# LVDS_IFCA.net
KiCad netlist of a schematic drawn in Altium Designer
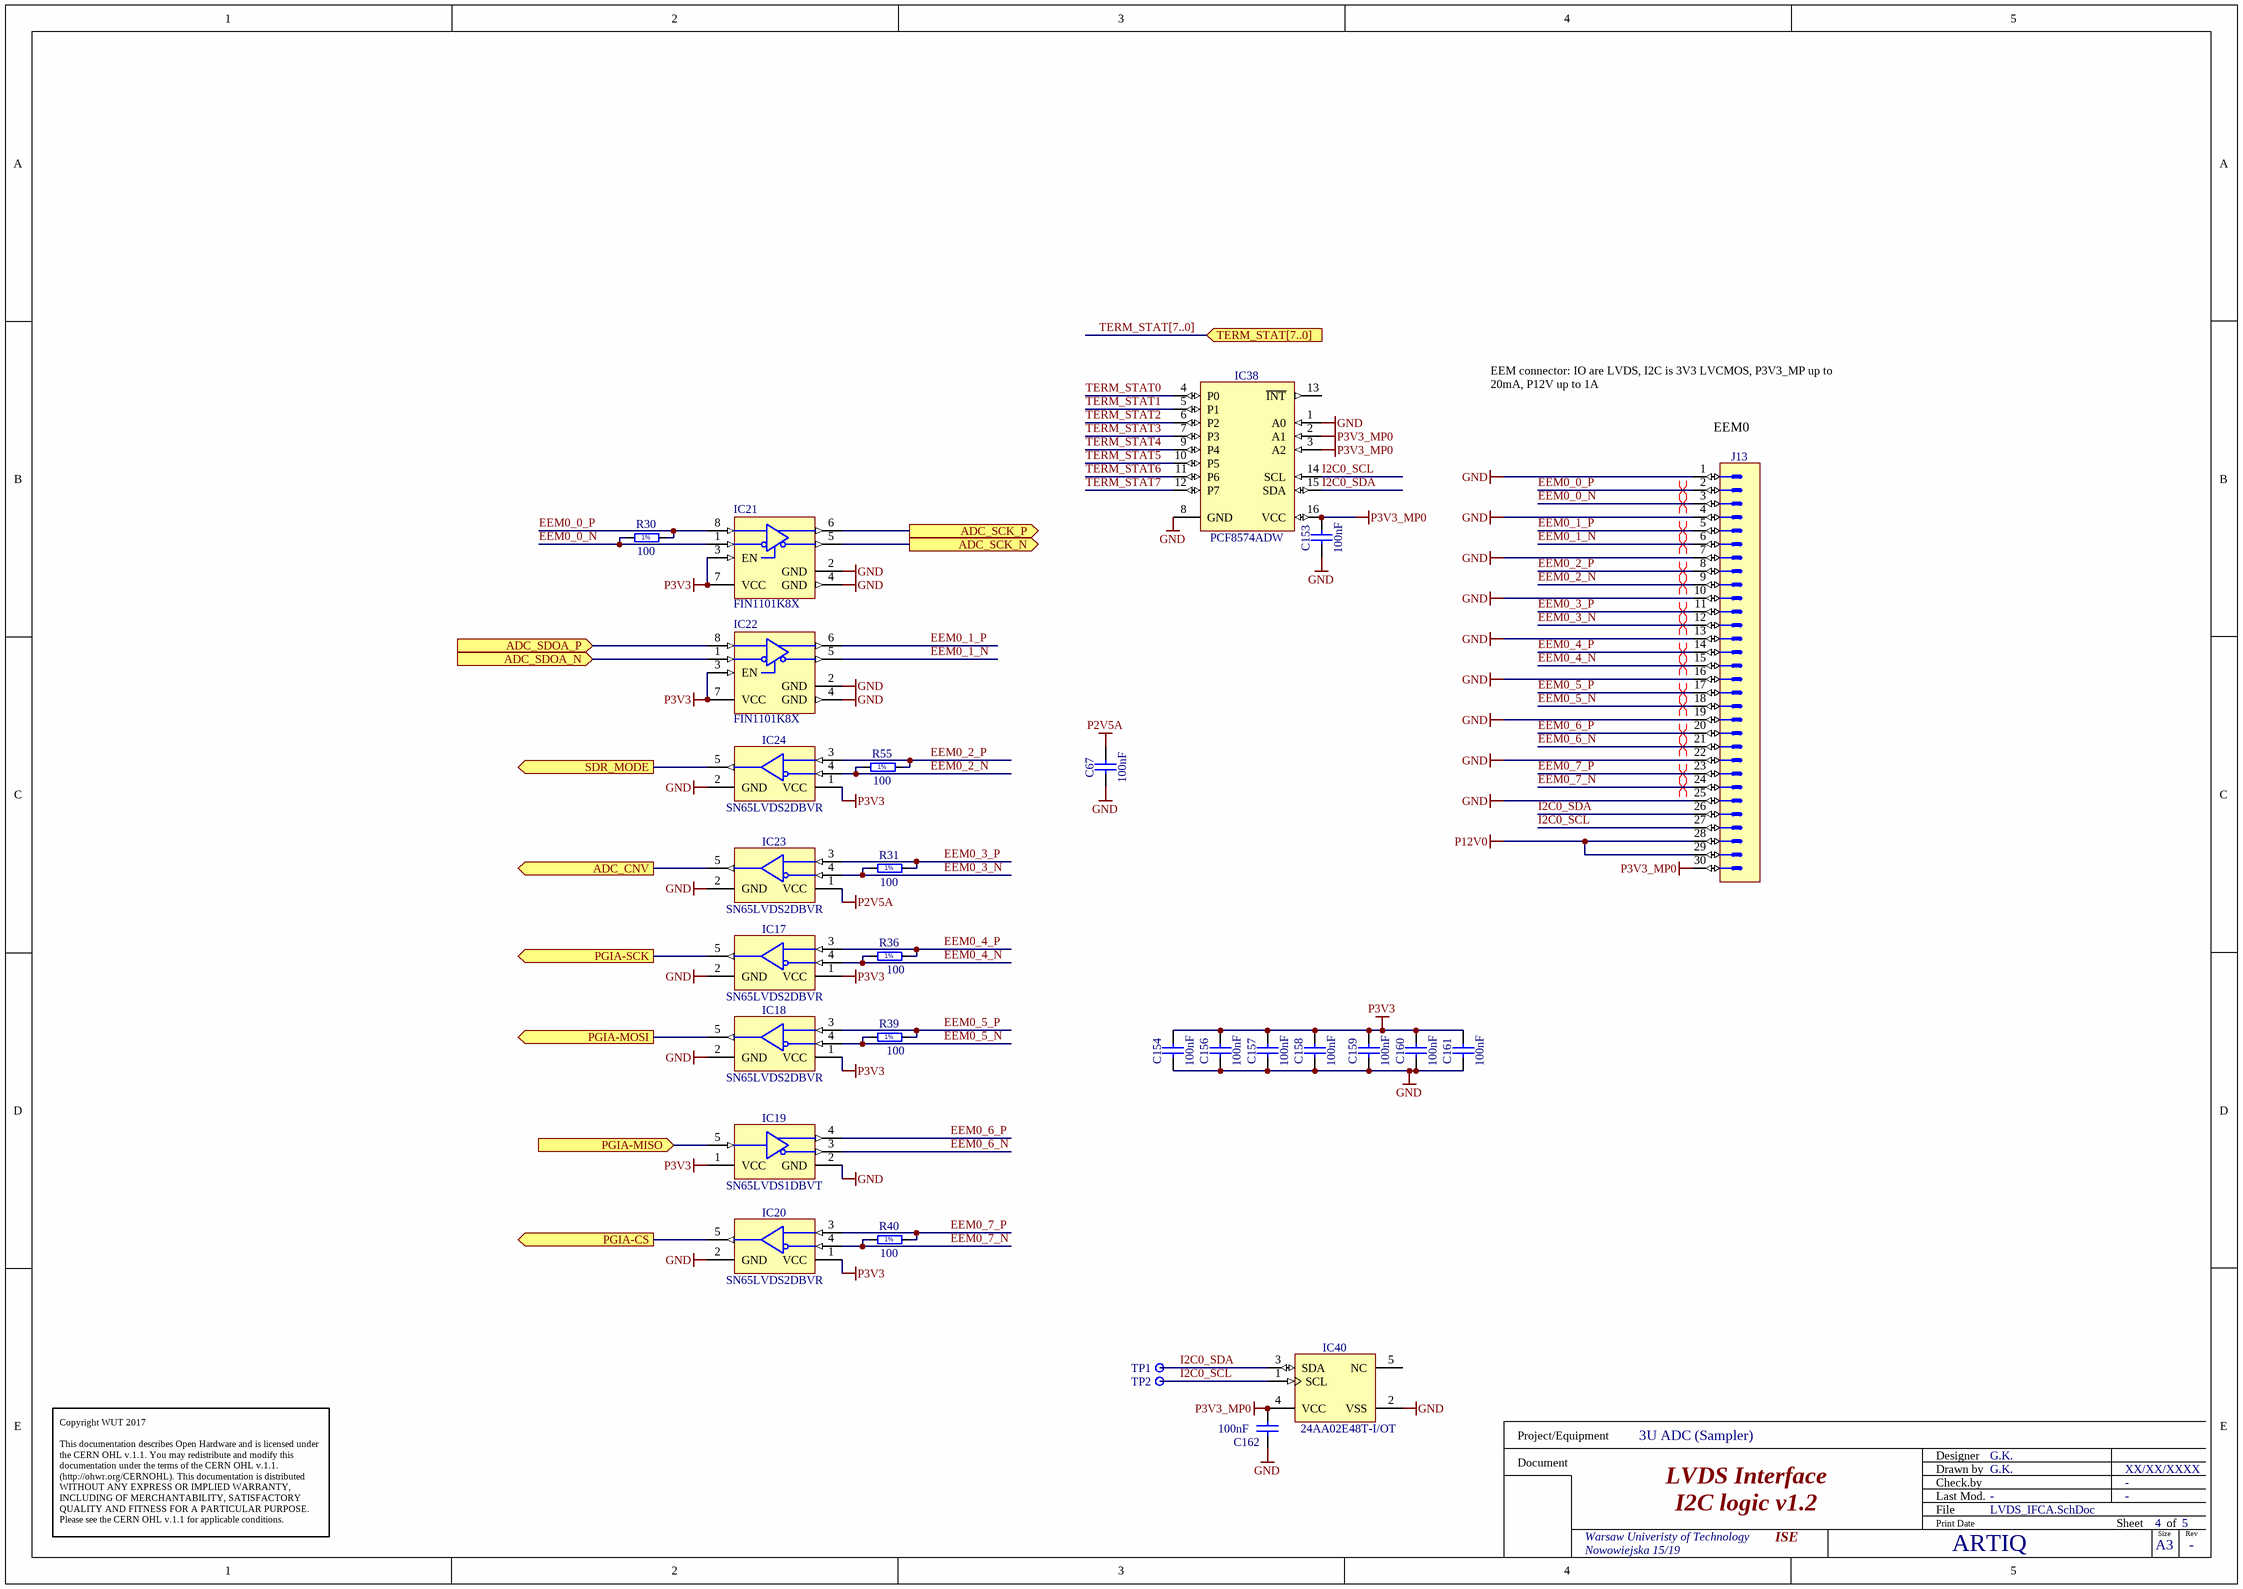
[diagram p0: LVDS_IFCA.SchDoc]

(export (version "E")
  (design (tool "Eeschema 10.0.6"))
  (components
    (comp (ref "C67")
      (value "100nF")
      (footprint "CAPC1005X55N")
      (description "Non-polarised capacitor")
      (fields
        (field (name "PART NUMBER") "CC0402_100NF_16V_10%_X5R")
        (field (name "VOLTAGE") "16V")
        (field (name "AUTHOR") "CERN DEM JLC")
      )
      (libsource (lib "Capacitors") (part "Capacitor - non polarized"))
    )
    (comp (ref "C153")
      (value "100nF")
      (footprint "CAPC1005X55N")
      (description "Non-polarised capacitor")
      (fields
        (field (name "PART NUMBER") "CC0402_100NF_16V_10%_X5R")
        (field (name "VOLTAGE") "16V")
        (field (name "AUTHOR") "CERN DEM JLC")
      )
      (libsource (lib "Capacitors") (part "Capacitor - non polarized"))
    )
    (comp (ref "C154")
      (value "100nF")
      (footprint "CAPC1005X55N")
      (description "Non-polarised capacitor")
      (fields
        (field (name "PART NUMBER") "CC0402_100NF_16V_10%_X5R")
        (field (name "VOLTAGE") "16V")
        (field (name "AUTHOR") "CERN DEM JLC")
      )
      (libsource (lib "Capacitors") (part "Capacitor - non polarized"))
    )
    (comp (ref "C156")
      (value "100nF")
      (footprint "CAPC1005X55N")
      (description "Non-polarised capacitor")
      (fields
        (field (name "PART NUMBER") "CC0402_100NF_16V_10%_X5R")
        (field (name "VOLTAGE") "16V")
        (field (name "AUTHOR") "CERN DEM JLC")
      )
      (libsource (lib "Capacitors") (part "Capacitor - non polarized"))
    )
    (comp (ref "C157")
      (value "100nF")
      (footprint "CAPC1005X55N")
      (description "Non-polarised capacitor")
      (fields
        (field (name "PART NUMBER") "CC0402_100NF_16V_10%_X5R")
        (field (name "VOLTAGE") "16V")
        (field (name "AUTHOR") "CERN DEM JLC")
      )
      (libsource (lib "Capacitors") (part "Capacitor - non polarized"))
    )
    (comp (ref "C158")
      (value "100nF")
      (footprint "CAPC1005X55N")
      (description "Non-polarised capacitor")
      (fields
        (field (name "PART NUMBER") "CC0402_100NF_16V_10%_X5R")
        (field (name "VOLTAGE") "16V")
        (field (name "AUTHOR") "CERN DEM JLC")
      )
      (libsource (lib "Capacitors") (part "Capacitor - non polarized"))
    )
    (comp (ref "C159")
      (value "100nF")
      (footprint "CAPC1005X55N")
      (description "Non-polarised capacitor")
      (fields
        (field (name "PART NUMBER") "CC0402_100NF_16V_10%_X5R")
        (field (name "VOLTAGE") "16V")
        (field (name "AUTHOR") "CERN DEM JLC")
      )
      (libsource (lib "Capacitors") (part "Capacitor - non polarized"))
    )
    (comp (ref "C160")
      (value "100nF")
      (footprint "CAPC1005X55N")
      (description "Non-polarised capacitor")
      (fields
        (field (name "PART NUMBER") "CC0402_100NF_16V_10%_X5R")
        (field (name "VOLTAGE") "16V")
        (field (name "AUTHOR") "CERN DEM JLC")
      )
      (libsource (lib "Capacitors") (part "Capacitor - non polarized"))
    )
    (comp (ref "C161")
      (value "100nF")
      (footprint "CAPC1005X55N")
      (description "Non-polarised capacitor")
      (fields
        (field (name "PART NUMBER") "CC0402_100NF_16V_10%_X5R")
        (field (name "VOLTAGE") "16V")
        (field (name "AUTHOR") "CERN DEM JLC")
      )
      (libsource (lib "Capacitors") (part "Capacitor - non polarized"))
    )
    (comp (ref "C162")
      (value "100nF")
      (footprint "CAPC1005X55N")
      (description "Non-polarised capacitor")
      (fields
        (field (name "PART NUMBER") "CC0402_100NF_16V_10%_X5R")
        (field (name "VOLTAGE") "16V")
        (field (name "AUTHOR") "CERN DEM JLC")
      )
      (libsource (lib "Capacitors") (part "Capacitor - non polarized"))
    )
    (comp (ref "IC17")
      (value "SN65LVDS2DBVR")
      (footprint "SOT95P280X145-5N")
      (description "High-Speed Differential Line Receiver")
      (fields (field (name "MANUFACTURER") "TEXAS INSTRUMENTS") (field (name "AUTHOR") "CERN DEM JLC"))
      (libsource (lib "ICs And Semiconductors") (part "SN65LVDS2DBV"))
    )
    (comp (ref "IC18")
      (value "SN65LVDS2DBVR")
      (footprint "SOT95P280X145-5N")
      (description "High-Speed Differential Line Receiver")
      (fields (field (name "MANUFACTURER") "TEXAS INSTRUMENTS") (field (name "AUTHOR") "CERN DEM JLC"))
      (libsource (lib "ICs And Semiconductors") (part "SN65LVDS2DBV"))
    )
    (comp (ref "IC19")
      (value "SN65LVDS1DBVT")
      (footprint "SOT95P280X145-5N")
      (description "High-Speed Differential Line Driver")
      (fields (field (name "MANUFACTURER") "TEXAS INSTRUMENTS") (field (name "AUTHOR") "CERN DEM JLC"))
      (libsource (lib "ICs And Semiconductors") (part "SN65LVDS1DBV"))
    )
    (comp (ref "IC20")
      (value "SN65LVDS2DBVR")
      (footprint "SOT95P280X145-5N")
      (description "High-Speed Differential Line Receiver")
      (fields (field (name "MANUFACTURER") "TEXAS INSTRUMENTS") (field (name "AUTHOR") "CERN DEM JLC"))
      (libsource (lib "ICs And Semiconductors") (part "SN65LVDS2DBV"))
    )
    (comp (ref "IC21")
      (value "FIN1101K8X")
      (footprint "SOP50P310X90-8N")
      (description "LVDS Single Port High Speed Repeater")
      (fields (field (name "MANUFACTURER") "FAIRCHILD SEMICONDUCTOR") (field (name "AUTHOR") "CERN DEM JLC"))
      (libsource (lib "ICs And Semiconductors") (part "FIN1101K8X"))
    )
    (comp (ref "IC22")
      (value "FIN1101K8X")
      (footprint "SOP50P310X90-8N")
      (description "LVDS Single Port High Speed Repeater")
      (fields (field (name "MANUFACTURER") "FAIRCHILD SEMICONDUCTOR") (field (name "AUTHOR") "CERN DEM JLC"))
      (libsource (lib "ICs And Semiconductors") (part "FIN1101K8X"))
    )
    (comp (ref "IC23")
      (value "SN65LVDS2DBVR")
      (footprint "SOT95P280X145-5N")
      (description "High-Speed Differential Line Receiver")
      (fields (field (name "MANUFACTURER") "TEXAS INSTRUMENTS") (field (name "AUTHOR") "CERN DEM JLC"))
      (libsource (lib "ICs And Semiconductors") (part "SN65LVDS2DBV"))
    )
    (comp (ref "IC24")
      (value "SN65LVDS2DBVR")
      (footprint "SOT95P280X145-5N")
      (description "High-Speed Differential Line Receiver")
      (fields (field (name "MANUFACTURER") "TEXAS INSTRUMENTS") (field (name "AUTHOR") "CERN DEM JLC"))
      (libsource (lib "ICs And Semiconductors") (part "SN65LVDS2DBV"))
    )
    (comp (ref "IC38")
      (value "PCF8574ADW")
      (footprint "SOIC127P1030X265-16N")
      (description "Remote 8-bit I/O Expander For I2C Bus")
      (fields (field (name "MANUFACTURER") "TEXAS INSTRUMENTS") (field (name "AUTHOR") "CERN DEM JLC"))
      (libsource (lib "ICs And Semiconductors") (part "PCF8574ADW"))
    )
    (comp (ref "IC40")
      (value "24AA02E48T-I/OT")
      (footprint "SOT95P280X145-5N")
      (description "1.7V-5.5V, 2K I2C Serial EEPROM With EUI-48 Node Identity")
      (fields (field (name "MANUFACTURER") "MICROCHIP TECHNOLOGY") (field (name "AUTHOR") "CERN DEM MR"))
      (libsource (lib "ICs And Semiconductors") (part "24AA02E48T-I/OT"))
    )
    (comp (ref "J13")
      (value "~")
      (footprint "3M_N2530-6002RB")
      (description "Connector 30 Male")
      (fields
        (field (name "PART NUMBER") "3M_N2530-6002RB")
        (field (name "MANUFACTURER") "3M")
        (field (name "AUTHOR") "CERN DEM JLC")
      )
      (libsource (lib "Connectors") (part "Connector 30 Male"))
    )
    (comp (ref "R30")
      (value "100")
      (footprint "RESC1005X40N")
      (description "Resistor - 1%")
      (fields
        (field (name "PART NUMBER") "R0402_100R_1%_0.1W_100PPM")
        (field (name "POWER") "0.1W")
        (field (name "AUTHOR") "CERN DEM JLC")
      )
      (libsource (lib "Resistors") (part "Resistor - 1%"))
    )
    (comp (ref "R31")
      (value "100")
      (footprint "RESC1005X40N")
      (description "Resistor - 1%")
      (fields
        (field (name "PART NUMBER") "R0402_100R_1%_0.1W_100PPM")
        (field (name "POWER") "0.1W")
        (field (name "AUTHOR") "CERN DEM JLC")
      )
      (libsource (lib "Resistors") (part "Resistor - 1%"))
    )
    (comp (ref "R36")
      (value "100")
      (footprint "RESC1005X40N")
      (description "Resistor - 1%")
      (fields
        (field (name "PART NUMBER") "R0402_100R_1%_0.1W_100PPM")
        (field (name "POWER") "0.1W")
        (field (name "AUTHOR") "CERN DEM JLC")
      )
      (libsource (lib "Resistors") (part "Resistor - 1%"))
    )
    (comp (ref "R39")
      (value "100")
      (footprint "RESC1005X40N")
      (description "Resistor - 1%")
      (fields
        (field (name "PART NUMBER") "R0402_100R_1%_0.1W_100PPM")
        (field (name "POWER") "0.1W")
        (field (name "AUTHOR") "CERN DEM JLC")
      )
      (libsource (lib "Resistors") (part "Resistor - 1%"))
    )
    (comp (ref "R40")
      (value "100")
      (footprint "RESC1005X40N")
      (description "Resistor - 1%")
      (fields
        (field (name "PART NUMBER") "R0402_100R_1%_0.1W_100PPM")
        (field (name "POWER") "0.1W")
        (field (name "AUTHOR") "CERN DEM JLC")
      )
      (libsource (lib "Resistors") (part "Resistor - 1%"))
    )
    (comp (ref "R55")
      (value "100")
      (footprint "RESC1005X40N")
      (description "Resistor - 1%")
      (fields
        (field (name "PART NUMBER") "R0402_100R_1%_0.1W_100PPM")
        (field (name "POWER") "0.1W")
        (field (name "AUTHOR") "CERN DEM JLC")
      )
      (libsource (lib "Resistors") (part "Resistor - 1%"))
    )
    (comp (ref "TP1")
      (value "Test Point")
      (footprint "TPS127")
      (fields (field (name "PART NUMBER") "SMD_PAD_1.27X1.27MM") (field (name "AUTHOR") "CERN DEM JLC"))
      (libsource (lib "Eletro-mechanical") (part "Test Point"))
    )
    (comp (ref "TP2")
      (value "Test Point")
      (footprint "TPS127")
      (fields (field (name "PART NUMBER") "SMD_PAD_1.27X1.27MM") (field (name "AUTHOR") "CERN DEM JLC"))
      (libsource (lib "Eletro-mechanical") (part "Test Point"))
    )
  )
  (nets
    (net (code "1") (name "/ADC_CNV") (class "Default")
      (node (ref "IC23") (pin "5") (pinfunction "R_5") (pintype "output"))
    )
    (net (code "2") (name "/ADC_SCK_N") (class "Default")
      (node (ref "IC21") (pin "5") (pinfunction "DOUT-_5") (pintype "output"))
    )
    (net (code "3") (name "/ADC_SCK_P") (class "Default")
      (node (ref "IC21") (pin "6") (pinfunction "DOUT+_6") (pintype "output"))
    )
    (net (code "4") (name "/ADC_SDOA_N") (class "Default")
      (node (ref "IC22") (pin "1") (pinfunction "RIN-_1") (pintype "input"))
    )
    (net (code "5") (name "/ADC_SDOA_P") (class "Default")
      (node (ref "IC22") (pin "8") (pinfunction "RIN+_8") (pintype "input"))
    )
    (net (code "6") (name "/EEM0_0_N") (class "Default")
      (node (ref "IC21") (pin "1") (pinfunction "RIN-_1") (pintype "input"))
      (node (ref "J13") (pin "3") (pinfunction "3_3") (pintype "bidirectional"))
      (node (ref "R30") (pin "1") (pinfunction "1_1") (pintype "passive"))
    )
    (net (code "7") (name "/EEM0_0_P") (class "Default")
      (node (ref "IC21") (pin "8") (pinfunction "RIN+_8") (pintype "input"))
      (node (ref "J13") (pin "2") (pinfunction "2_2") (pintype "bidirectional"))
      (node (ref "R30") (pin "2") (pinfunction "2_2") (pintype "passive"))
    )
    (net (code "8") (name "/EEM0_1_N") (class "Default")
      (node (ref "IC22") (pin "5") (pinfunction "DOUT-_5") (pintype "output"))
      (node (ref "J13") (pin "6") (pinfunction "6_6") (pintype "bidirectional"))
    )
    (net (code "9") (name "/EEM0_1_P") (class "Default")
      (node (ref "IC22") (pin "6") (pinfunction "DOUT+_6") (pintype "output"))
      (node (ref "J13") (pin "5") (pinfunction "5_5") (pintype "bidirectional"))
    )
    (net (code "10") (name "/EEM0_2_N") (class "Default")
      (node (ref "IC24") (pin "4") (pinfunction "B_4") (pintype "input"))
      (node (ref "J13") (pin "9") (pinfunction "9_9") (pintype "bidirectional"))
      (node (ref "R55") (pin "1") (pinfunction "1_1") (pintype "passive"))
    )
    (net (code "11") (name "/EEM0_2_P") (class "Default")
      (node (ref "IC24") (pin "3") (pinfunction "A_3") (pintype "input"))
      (node (ref "J13") (pin "8") (pinfunction "8_8") (pintype "bidirectional"))
      (node (ref "R55") (pin "2") (pinfunction "2_2") (pintype "passive"))
    )
    (net (code "12") (name "/EEM0_3_N") (class "Default")
      (node (ref "IC23") (pin "4") (pinfunction "B_4") (pintype "input"))
      (node (ref "J13") (pin "12") (pinfunction "12_12") (pintype "bidirectional"))
      (node (ref "R31") (pin "1") (pinfunction "1_1") (pintype "passive"))
    )
    (net (code "13") (name "/EEM0_3_P") (class "Default")
      (node (ref "IC23") (pin "3") (pinfunction "A_3") (pintype "input"))
      (node (ref "J13") (pin "11") (pinfunction "11_11") (pintype "bidirectional"))
      (node (ref "R31") (pin "2") (pinfunction "2_2") (pintype "passive"))
    )
    (net (code "14") (name "/EEM0_4_N") (class "Default")
      (node (ref "IC17") (pin "4") (pinfunction "B_4") (pintype "input"))
      (node (ref "J13") (pin "15") (pinfunction "15_15") (pintype "bidirectional"))
      (node (ref "R36") (pin "1") (pinfunction "1_1") (pintype "passive"))
    )
    (net (code "15") (name "/EEM0_4_P") (class "Default")
      (node (ref "IC17") (pin "3") (pinfunction "A_3") (pintype "input"))
      (node (ref "J13") (pin "14") (pinfunction "14_14") (pintype "bidirectional"))
      (node (ref "R36") (pin "2") (pinfunction "2_2") (pintype "passive"))
    )
    (net (code "16") (name "/EEM0_5_N") (class "Default")
      (node (ref "IC18") (pin "4") (pinfunction "B_4") (pintype "input"))
      (node (ref "J13") (pin "18") (pinfunction "18_18") (pintype "bidirectional"))
      (node (ref "R39") (pin "1") (pinfunction "1_1") (pintype "passive"))
    )
    (net (code "17") (name "/EEM0_5_P") (class "Default")
      (node (ref "IC18") (pin "3") (pinfunction "A_3") (pintype "input"))
      (node (ref "J13") (pin "17") (pinfunction "17_17") (pintype "bidirectional"))
      (node (ref "R39") (pin "2") (pinfunction "2_2") (pintype "passive"))
    )
    (net (code "18") (name "/EEM0_6_N") (class "Default")
      (node (ref "IC19") (pin "3") (pinfunction "A_3") (pintype "output"))
      (node (ref "J13") (pin "21") (pinfunction "21_21") (pintype "bidirectional"))
    )
    (net (code "19") (name "/EEM0_6_P") (class "Default")
      (node (ref "IC19") (pin "4") (pinfunction "B_4") (pintype "output"))
      (node (ref "J13") (pin "20") (pinfunction "20_20") (pintype "bidirectional"))
    )
    (net (code "20") (name "/EEM0_7_N") (class "Default")
      (node (ref "IC20") (pin "4") (pinfunction "B_4") (pintype "input"))
      (node (ref "J13") (pin "24") (pinfunction "24_24") (pintype "bidirectional"))
      (node (ref "R40") (pin "1") (pinfunction "1_1") (pintype "passive"))
    )
    (net (code "21") (name "/EEM0_7_P") (class "Default")
      (node (ref "IC20") (pin "3") (pinfunction "A_3") (pintype "input"))
      (node (ref "J13") (pin "23") (pinfunction "23_23") (pintype "bidirectional"))
      (node (ref "R40") (pin "2") (pinfunction "2_2") (pintype "passive"))
    )
    (net (code "22") (name "/I2C0_SCL") (class "Default")
      (node (ref "IC38") (pin "14") (pinfunction "SCL_14") (pintype "input"))
      (node (ref "IC40") (pin "1") (pinfunction "SCL_1") (pintype "input"))
      (node (ref "J13") (pin "27") (pinfunction "27_27") (pintype "bidirectional"))
      (node (ref "TP2") (pin "1") (pinfunction "1_1") (pintype "bidirectional"))
    )
    (net (code "23") (name "/I2C0_SDA") (class "Default")
      (node (ref "IC38") (pin "15") (pinfunction "SDA_15") (pintype "bidirectional"))
      (node (ref "IC40") (pin "3") (pinfunction "SDA_3") (pintype "bidirectional"))
      (node (ref "J13") (pin "26") (pinfunction "26_26") (pintype "bidirectional"))
      (node (ref "TP1") (pin "1") (pinfunction "1_1") (pintype "bidirectional"))
    )
    (net (code "24") (name "/PGIA-CS") (class "Default")
      (node (ref "IC20") (pin "5") (pinfunction "R_5") (pintype "output"))
    )
    (net (code "25") (name "/PGIA-MISO") (class "Default")
      (node (ref "IC19") (pin "5") (pinfunction "R_5") (pintype "input"))
    )
    (net (code "26") (name "/PGIA-MOSI") (class "Default")
      (node (ref "IC18") (pin "5") (pinfunction "R_5") (pintype "output"))
    )
    (net (code "27") (name "/PGIA-SCK") (class "Default")
      (node (ref "IC17") (pin "5") (pinfunction "R_5") (pintype "output"))
    )
    (net (code "28") (name "/SDR_MODE") (class "Default")
      (node (ref "IC24") (pin "5") (pinfunction "R_5") (pintype "output"))
    )
    (net (code "29") (name "/TERM_STAT0") (class "Default")
      (node (ref "IC38") (pin "4") (pinfunction "P0_4") (pintype "bidirectional"))
    )
    (net (code "30") (name "/TERM_STAT1") (class "Default")
      (node (ref "IC38") (pin "5") (pinfunction "P1_5") (pintype "bidirectional"))
    )
    (net (code "31") (name "/TERM_STAT2") (class "Default")
      (node (ref "IC38") (pin "6") (pinfunction "P2_6") (pintype "bidirectional"))
    )
    (net (code "32") (name "/TERM_STAT3") (class "Default")
      (node (ref "IC38") (pin "7") (pinfunction "P3_7") (pintype "bidirectional"))
    )
    (net (code "33") (name "/TERM_STAT4") (class "Default")
      (node (ref "IC38") (pin "9") (pinfunction "P4_9") (pintype "bidirectional"))
    )
    (net (code "34") (name "/TERM_STAT5") (class "Default")
      (node (ref "IC38") (pin "10") (pinfunction "P5_10") (pintype "bidirectional"))
    )
    (net (code "35") (name "/TERM_STAT6") (class "Default")
      (node (ref "IC38") (pin "11") (pinfunction "P6_11") (pintype "bidirectional"))
    )
    (net (code "36") (name "/TERM_STAT7") (class "Default")
      (node (ref "IC38") (pin "12") (pinfunction "P7_12") (pintype "bidirectional"))
    )
    (net (code "38") (name "GND") (class "Default")
      (node (ref "C153") (pin "1") (pinfunction "1_1") (pintype "passive"))
      (node (ref "C154") (pin "1") (pinfunction "1_1") (pintype "passive"))
      (node (ref "C156") (pin "1") (pinfunction "1_1") (pintype "passive"))
      (node (ref "C157") (pin "1") (pinfunction "1_1") (pintype "passive"))
      (node (ref "C158") (pin "1") (pinfunction "1_1") (pintype "passive"))
      (node (ref "C159") (pin "1") (pinfunction "1_1") (pintype "passive"))
      (node (ref "C160") (pin "1") (pinfunction "1_1") (pintype "passive"))
      (node (ref "C161") (pin "1") (pinfunction "1_1") (pintype "passive"))
      (node (ref "C162") (pin "1") (pinfunction "1_1") (pintype "passive"))
      (node (ref "C67") (pin "1") (pinfunction "1_1") (pintype "passive"))
      (node (ref "IC17") (pin "2") (pinfunction "GND_2") (pintype "power_in"))
      (node (ref "IC18") (pin "2") (pinfunction "GND_2") (pintype "power_in"))
      (node (ref "IC19") (pin "2") (pinfunction "GND_2") (pintype "power_in"))
      (node (ref "IC20") (pin "2") (pinfunction "GND_2") (pintype "power_in"))
      (node (ref "IC21") (pin "2") (pinfunction "GND_2") (pintype "power_in"))
      (node (ref "IC21") (pin "4") (pinfunction "GND_4") (pintype "output"))
      (node (ref "IC22") (pin "2") (pinfunction "GND_2") (pintype "power_in"))
      (node (ref "IC22") (pin "4") (pinfunction "GND_4") (pintype "output"))
      (node (ref "IC23") (pin "2") (pinfunction "GND_2") (pintype "power_in"))
      (node (ref "IC24") (pin "2") (pinfunction "GND_2") (pintype "power_in"))
      (node (ref "IC38") (pin "1") (pinfunction "A0_1") (pintype "input"))
      (node (ref "IC38") (pin "8") (pinfunction "GND_8") (pintype "power_in"))
      (node (ref "IC40") (pin "2") (pinfunction "VSS_2") (pintype "power_in"))
      (node (ref "J13") (pin "1") (pinfunction "1_1") (pintype "bidirectional"))
      (node (ref "J13") (pin "10") (pinfunction "10_10") (pintype "bidirectional"))
      (node (ref "J13") (pin "13") (pinfunction "13_13") (pintype "bidirectional"))
      (node (ref "J13") (pin "16") (pinfunction "16_16") (pintype "bidirectional"))
      (node (ref "J13") (pin "19") (pinfunction "19_19") (pintype "bidirectional"))
      (node (ref "J13") (pin "22") (pinfunction "22_22") (pintype "bidirectional"))
      (node (ref "J13") (pin "25") (pinfunction "25_25") (pintype "bidirectional"))
      (node (ref "J13") (pin "4") (pinfunction "4_4") (pintype "bidirectional"))
      (node (ref "J13") (pin "7") (pinfunction "7_7") (pintype "bidirectional"))
    )
    (net (code "39") (name "P2V5A") (class "Default")
      (node (ref "C67") (pin "2") (pinfunction "2_2") (pintype "passive"))
      (node (ref "IC23") (pin "1") (pinfunction "VCC_1") (pintype "power_in"))
    )
    (net (code "40") (name "P3V3") (class "Default")
      (node (ref "C154") (pin "2") (pinfunction "2_2") (pintype "passive"))
      (node (ref "C156") (pin "2") (pinfunction "2_2") (pintype "passive"))
      (node (ref "C157") (pin "2") (pinfunction "2_2") (pintype "passive"))
      (node (ref "C158") (pin "2") (pinfunction "2_2") (pintype "passive"))
      (node (ref "C159") (pin "2") (pinfunction "2_2") (pintype "passive"))
      (node (ref "C160") (pin "2") (pinfunction "2_2") (pintype "passive"))
      (node (ref "C161") (pin "2") (pinfunction "2_2") (pintype "passive"))
      (node (ref "IC17") (pin "1") (pinfunction "VCC_1") (pintype "power_in"))
      (node (ref "IC18") (pin "1") (pinfunction "VCC_1") (pintype "power_in"))
      (node (ref "IC19") (pin "1") (pinfunction "VCC_1") (pintype "power_in"))
      (node (ref "IC20") (pin "1") (pinfunction "VCC_1") (pintype "power_in"))
      (node (ref "IC21") (pin "3") (pinfunction "EN_3") (pintype "input"))
      (node (ref "IC21") (pin "7") (pinfunction "VCC_7") (pintype "power_in"))
      (node (ref "IC22") (pin "3") (pinfunction "EN_3") (pintype "input"))
      (node (ref "IC22") (pin "7") (pinfunction "VCC_7") (pintype "power_in"))
      (node (ref "IC24") (pin "1") (pinfunction "VCC_1") (pintype "power_in"))
    )
    (net (code "41") (name "P3V3_MP0") (class "Default")
      (node (ref "C153") (pin "2") (pinfunction "2_2") (pintype "passive"))
      (node (ref "C162") (pin "2") (pinfunction "2_2") (pintype "passive"))
      (node (ref "IC38") (pin "16") (pinfunction "VCC_16") (pintype "bidirectional"))
      (node (ref "IC38") (pin "2") (pinfunction "A1_2") (pintype "input"))
      (node (ref "IC38") (pin "3") (pinfunction "A2_3") (pintype "input"))
      (node (ref "IC40") (pin "4") (pinfunction "VCC_4") (pintype "power_in"))
      (node (ref "J13") (pin "30") (pinfunction "30_30") (pintype "bidirectional"))
    )
    (net (code "42") (name "P12V0") (class "Default")
      (node (ref "J13") (pin "28") (pinfunction "28_28") (pintype "bidirectional"))
      (node (ref "J13") (pin "29") (pinfunction "29_29") (pintype "bidirectional"))
    )
    (net (code "43") (name "unconnected-(IC38-~{INT}-Pad13)") (class "Default")
      (node (ref "IC38") (pin "13") (pinfunction "~{INT}_13") (pintype "output"))
    )
    (net (code "44") (name "unconnected-(IC40-NC-Pad5)") (class "Default")
      (node (ref "IC40") (pin "5") (pinfunction "NC_5") (pintype "passive"))
    )
  )
)
